# snesbotv2.net
KiCad netlist of a schematic drawn in EAGLE
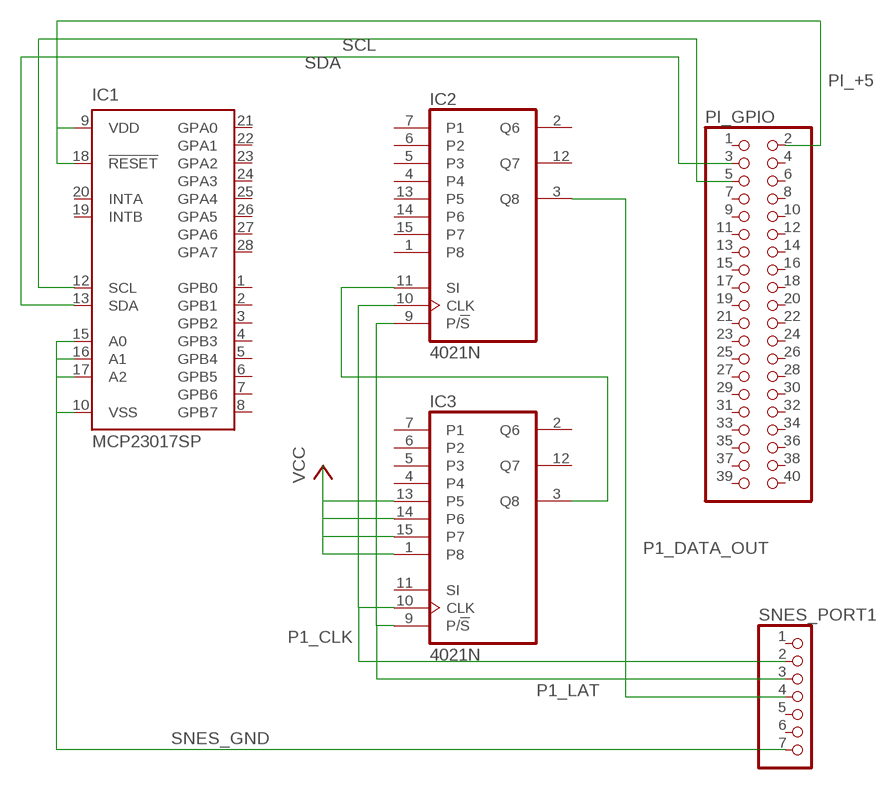
[diagram p0: schematic, sheet 1]

(export (version "E")
  (design (tool "Eeschema 10.0.6"))
  (components
    (comp (ref "IC1")
      (value "MCP23017SP")
      (footprint "eagle-import:DIL28-3")
      (libsource (lib "eagle-import") (part "MCP23017SP"))
    )
    (comp (ref "IC2")
      (value "4021N")
      (footprint "eagle-import:DIL16")
      (libsource (lib "eagle-import") (part "4021N"))
    )
    (comp (ref "IC3")
      (value "4021N")
      (footprint "eagle-import:DIL16")
      (libsource (lib "eagle-import") (part "4021N"))
    )
    (comp (ref "PI_GPIO")
      (value "PINHD-2X20")
      (footprint "eagle-import:2X20")
      (libsource (lib "eagle-import") (part "PINHD-2X20"))
    )
    (comp (ref "SNES_PORT1")
      (value "PINHD-1X7")
      (footprint "eagle-import:1X07")
      (libsource (lib "eagle-import") (part "PINHD-1X7"))
    )
  )
  (nets
    (net (code "1") (name "/P1_CLK") (class "Default")
      (node (ref "IC2") (pin "10") (pinfunction "CLK_10") (pintype "input"))
      (node (ref "IC3") (pin "10") (pinfunction "CLK_10") (pintype "input"))
      (node (ref "SNES_PORT1") (pin "2") (pinfunction "2_2") (pintype "passive"))
    )
    (net (code "2") (name "/P1_DATA_OUT") (class "Default")
      (node (ref "IC2") (pin "3") (pinfunction "Q8_3") (pintype "output"))
      (node (ref "SNES_PORT1") (pin "4") (pinfunction "4_4") (pintype "passive"))
    )
    (net (code "3") (name "/P1_LAT") (class "Default")
      (node (ref "IC2") (pin "9") (pinfunction "P/~{S}_9") (pintype "input"))
      (node (ref "IC3") (pin "9") (pinfunction "P/~{S}_9") (pintype "input"))
      (node (ref "SNES_PORT1") (pin "3") (pinfunction "3_3") (pintype "passive"))
    )
    (net (code "4") (name "/PI_+5") (class "Default")
      (node (ref "IC1") (pin "18") (pinfunction "~{RESET}_18") (pintype "input"))
      (node (ref "IC1") (pin "9") (pinfunction "VDD_9") (pintype "power_in"))
      (node (ref "PI_GPIO") (pin "2") (pinfunction "2_2") (pintype "passive"))
    )
    (net (code "5") (name "/SCL") (class "Default")
      (node (ref "IC1") (pin "12") (pinfunction "SCL_12") (pintype "input"))
      (node (ref "PI_GPIO") (pin "5") (pinfunction "5_5") (pintype "passive"))
    )
    (net (code "6") (name "/SDA") (class "Default")
      (node (ref "IC1") (pin "13") (pinfunction "SDA_13") (pintype "bidirectional"))
      (node (ref "PI_GPIO") (pin "3") (pinfunction "3_3") (pintype "passive"))
    )
    (net (code "7") (name "/SNES_GND") (class "Default")
      (node (ref "IC1") (pin "10") (pinfunction "VSS_10") (pintype "power_in"))
      (node (ref "IC1") (pin "15") (pinfunction "A0_15") (pintype "input"))
      (node (ref "IC1") (pin "16") (pinfunction "A1_16") (pintype "input"))
      (node (ref "IC1") (pin "17") (pinfunction "A2_17") (pintype "input"))
      (node (ref "SNES_PORT1") (pin "7") (pinfunction "7_7") (pintype "passive"))
    )
    (net (code "8") (name "Net-(IC2A-SI)") (class "Default")
      (node (ref "IC2") (pin "11") (pinfunction "SI_11") (pintype "input"))
      (node (ref "IC3") (pin "3") (pinfunction "Q8_3") (pintype "output"))
    )
    (net (code "9") (name "Net-(IC3A-P5)") (class "Default")
      (node (ref "IC3") (pin "1") (pinfunction "P8_1") (pintype "input"))
      (node (ref "IC3") (pin "13") (pinfunction "P5_13") (pintype "input"))
      (node (ref "IC3") (pin "14") (pinfunction "P6_14") (pintype "input"))
      (node (ref "IC3") (pin "15") (pinfunction "P7_15") (pintype "input"))
    )
    (net (code "11") (name "unconnected-(IC1-GPA0-Pad21)") (class "Default")
      (node (ref "IC1") (pin "21") (pinfunction "GPA0_21") (pintype "bidirectional"))
    )
    (net (code "12") (name "unconnected-(IC1-GPA1-Pad22)") (class "Default")
      (node (ref "IC1") (pin "22") (pinfunction "GPA1_22") (pintype "bidirectional"))
    )
    (net (code "13") (name "unconnected-(IC1-GPA2-Pad23)") (class "Default")
      (node (ref "IC1") (pin "23") (pinfunction "GPA2_23") (pintype "bidirectional"))
    )
    (net (code "14") (name "unconnected-(IC1-GPA3-Pad24)") (class "Default")
      (node (ref "IC1") (pin "24") (pinfunction "GPA3_24") (pintype "bidirectional"))
    )
    (net (code "15") (name "unconnected-(IC1-GPA4-Pad25)") (class "Default")
      (node (ref "IC1") (pin "25") (pinfunction "GPA4_25") (pintype "bidirectional"))
    )
    (net (code "16") (name "unconnected-(IC1-GPA5-Pad26)") (class "Default")
      (node (ref "IC1") (pin "26") (pinfunction "GPA5_26") (pintype "bidirectional"))
    )
    (net (code "17") (name "unconnected-(IC1-GPA6-Pad27)") (class "Default")
      (node (ref "IC1") (pin "27") (pinfunction "GPA6_27") (pintype "bidirectional"))
    )
    (net (code "18") (name "unconnected-(IC1-GPA7-Pad28)") (class "Default")
      (node (ref "IC1") (pin "28") (pinfunction "GPA7_28") (pintype "bidirectional"))
    )
    (net (code "19") (name "unconnected-(IC1-GPB0-Pad1)") (class "Default")
      (node (ref "IC1") (pin "1") (pinfunction "GPB0_1") (pintype "bidirectional"))
    )
    (net (code "20") (name "unconnected-(IC1-GPB1-Pad2)") (class "Default")
      (node (ref "IC1") (pin "2") (pinfunction "GPB1_2") (pintype "bidirectional"))
    )
    (net (code "21") (name "unconnected-(IC1-GPB2-Pad3)") (class "Default")
      (node (ref "IC1") (pin "3") (pinfunction "GPB2_3") (pintype "bidirectional"))
    )
    (net (code "22") (name "unconnected-(IC1-GPB3-Pad4)") (class "Default")
      (node (ref "IC1") (pin "4") (pinfunction "GPB3_4") (pintype "bidirectional"))
    )
    (net (code "23") (name "unconnected-(IC1-GPB4-Pad5)") (class "Default")
      (node (ref "IC1") (pin "5") (pinfunction "GPB4_5") (pintype "bidirectional"))
    )
    (net (code "24") (name "unconnected-(IC1-GPB5-Pad6)") (class "Default")
      (node (ref "IC1") (pin "6") (pinfunction "GPB5_6") (pintype "bidirectional"))
    )
    (net (code "25") (name "unconnected-(IC1-GPB6-Pad7)") (class "Default")
      (node (ref "IC1") (pin "7") (pinfunction "GPB6_7") (pintype "bidirectional"))
    )
    (net (code "26") (name "unconnected-(IC1-GPB7-Pad8)") (class "Default")
      (node (ref "IC1") (pin "8") (pinfunction "GPB7_8") (pintype "bidirectional"))
    )
    (net (code "27") (name "unconnected-(IC1-INTA-Pad20)") (class "Default")
      (node (ref "IC1") (pin "20") (pinfunction "INTA_20") (pintype "output"))
    )
    (net (code "28") (name "unconnected-(IC1-INTB-Pad19)") (class "Default")
      (node (ref "IC1") (pin "19") (pinfunction "INTB_19") (pintype "output"))
    )
    (net (code "29") (name "unconnected-(IC2A-P1-Pad7)") (class "Default")
      (node (ref "IC2") (pin "7") (pinfunction "P1_7") (pintype "input"))
    )
    (net (code "30") (name "unconnected-(IC2A-P2-Pad6)") (class "Default")
      (node (ref "IC2") (pin "6") (pinfunction "P2_6") (pintype "input"))
    )
    (net (code "31") (name "unconnected-(IC2A-P3-Pad5)") (class "Default")
      (node (ref "IC2") (pin "5") (pinfunction "P3_5") (pintype "input"))
    )
    (net (code "32") (name "unconnected-(IC2A-P4-Pad4)") (class "Default")
      (node (ref "IC2") (pin "4") (pinfunction "P4_4") (pintype "input"))
    )
    (net (code "33") (name "unconnected-(IC2A-P5-Pad13)") (class "Default")
      (node (ref "IC2") (pin "13") (pinfunction "P5_13") (pintype "input"))
    )
    (net (code "34") (name "unconnected-(IC2A-P6-Pad14)") (class "Default")
      (node (ref "IC2") (pin "14") (pinfunction "P6_14") (pintype "input"))
    )
    (net (code "35") (name "unconnected-(IC2A-P7-Pad15)") (class "Default")
      (node (ref "IC2") (pin "15") (pinfunction "P7_15") (pintype "input"))
    )
    (net (code "36") (name "unconnected-(IC2A-P8-Pad1)") (class "Default")
      (node (ref "IC2") (pin "1") (pinfunction "P8_1") (pintype "input"))
    )
    (net (code "37") (name "unconnected-(IC2A-Q6-Pad2)") (class "Default")
      (node (ref "IC2") (pin "2") (pinfunction "Q6_2") (pintype "output"))
    )
    (net (code "38") (name "unconnected-(IC2A-Q7-Pad12)") (class "Default")
      (node (ref "IC2") (pin "12") (pinfunction "Q7_12") (pintype "output"))
    )
    (net (code "39") (name "unconnected-(IC3A-P1-Pad7)") (class "Default")
      (node (ref "IC3") (pin "7") (pinfunction "P1_7") (pintype "input"))
    )
    (net (code "40") (name "unconnected-(IC3A-P2-Pad6)") (class "Default")
      (node (ref "IC3") (pin "6") (pinfunction "P2_6") (pintype "input"))
    )
    (net (code "41") (name "unconnected-(IC3A-P3-Pad5)") (class "Default")
      (node (ref "IC3") (pin "5") (pinfunction "P3_5") (pintype "input"))
    )
    (net (code "42") (name "unconnected-(IC3A-P4-Pad4)") (class "Default")
      (node (ref "IC3") (pin "4") (pinfunction "P4_4") (pintype "input"))
    )
    (net (code "43") (name "unconnected-(IC3A-Q6-Pad2)") (class "Default")
      (node (ref "IC3") (pin "2") (pinfunction "Q6_2") (pintype "output"))
    )
    (net (code "44") (name "unconnected-(IC3A-Q7-Pad12)") (class "Default")
      (node (ref "IC3") (pin "12") (pinfunction "Q7_12") (pintype "output"))
    )
    (net (code "45") (name "unconnected-(IC3A-SI-Pad11)") (class "Default")
      (node (ref "IC3") (pin "11") (pinfunction "SI_11") (pintype "input"))
    )
    (net (code "46") (name "unconnected-(PI_GPIO-Pad1)") (class "Default")
      (node (ref "PI_GPIO") (pin "1") (pinfunction "1_1") (pintype "passive"))
    )
    (net (code "47") (name "unconnected-(PI_GPIO-Pad4)") (class "Default")
      (node (ref "PI_GPIO") (pin "4") (pinfunction "4_4") (pintype "passive"))
    )
    (net (code "48") (name "unconnected-(PI_GPIO-Pad6)") (class "Default")
      (node (ref "PI_GPIO") (pin "6") (pinfunction "6_6") (pintype "passive"))
    )
    (net (code "49") (name "unconnected-(PI_GPIO-Pad7)") (class "Default")
      (node (ref "PI_GPIO") (pin "7") (pinfunction "7_7") (pintype "passive"))
    )
    (net (code "50") (name "unconnected-(PI_GPIO-Pad8)") (class "Default")
      (node (ref "PI_GPIO") (pin "8") (pinfunction "8_8") (pintype "passive"))
    )
    (net (code "51") (name "unconnected-(PI_GPIO-Pad9)") (class "Default")
      (node (ref "PI_GPIO") (pin "9") (pinfunction "9_9") (pintype "passive"))
    )
    (net (code "52") (name "unconnected-(PI_GPIO-Pad10)") (class "Default")
      (node (ref "PI_GPIO") (pin "10") (pinfunction "10_10") (pintype "passive"))
    )
    (net (code "53") (name "unconnected-(PI_GPIO-Pad11)") (class "Default")
      (node (ref "PI_GPIO") (pin "11") (pinfunction "11_11") (pintype "passive"))
    )
    (net (code "54") (name "unconnected-(PI_GPIO-Pad12)") (class "Default")
      (node (ref "PI_GPIO") (pin "12") (pinfunction "12_12") (pintype "passive"))
    )
    (net (code "55") (name "unconnected-(PI_GPIO-Pad13)") (class "Default")
      (node (ref "PI_GPIO") (pin "13") (pinfunction "13_13") (pintype "passive"))
    )
    (net (code "56") (name "unconnected-(PI_GPIO-Pad14)") (class "Default")
      (node (ref "PI_GPIO") (pin "14") (pinfunction "14_14") (pintype "passive"))
    )
    (net (code "57") (name "unconnected-(PI_GPIO-Pad15)") (class "Default")
      (node (ref "PI_GPIO") (pin "15") (pinfunction "15_15") (pintype "passive"))
    )
    (net (code "58") (name "unconnected-(PI_GPIO-Pad16)") (class "Default")
      (node (ref "PI_GPIO") (pin "16") (pinfunction "16_16") (pintype "passive"))
    )
    (net (code "59") (name "unconnected-(PI_GPIO-Pad17)") (class "Default")
      (node (ref "PI_GPIO") (pin "17") (pinfunction "17_17") (pintype "passive"))
    )
    (net (code "60") (name "unconnected-(PI_GPIO-Pad18)") (class "Default")
      (node (ref "PI_GPIO") (pin "18") (pinfunction "18_18") (pintype "passive"))
    )
    (net (code "61") (name "unconnected-(PI_GPIO-Pad19)") (class "Default")
      (node (ref "PI_GPIO") (pin "19") (pinfunction "19_19") (pintype "passive"))
    )
    (net (code "62") (name "unconnected-(PI_GPIO-Pad20)") (class "Default")
      (node (ref "PI_GPIO") (pin "20") (pinfunction "20_20") (pintype "passive"))
    )
    (net (code "63") (name "unconnected-(PI_GPIO-Pad21)") (class "Default")
      (node (ref "PI_GPIO") (pin "21") (pinfunction "21_21") (pintype "passive"))
    )
    (net (code "64") (name "unconnected-(PI_GPIO-Pad22)") (class "Default")
      (node (ref "PI_GPIO") (pin "22") (pinfunction "22_22") (pintype "passive"))
    )
    (net (code "65") (name "unconnected-(PI_GPIO-Pad23)") (class "Default")
      (node (ref "PI_GPIO") (pin "23") (pinfunction "23_23") (pintype "passive"))
    )
    (net (code "66") (name "unconnected-(PI_GPIO-Pad24)") (class "Default")
      (node (ref "PI_GPIO") (pin "24") (pinfunction "24_24") (pintype "passive"))
    )
    (net (code "67") (name "unconnected-(PI_GPIO-Pad25)") (class "Default")
      (node (ref "PI_GPIO") (pin "25") (pinfunction "25_25") (pintype "passive"))
    )
    (net (code "68") (name "unconnected-(PI_GPIO-Pad26)") (class "Default")
      (node (ref "PI_GPIO") (pin "26") (pinfunction "26_26") (pintype "passive"))
    )
    (net (code "69") (name "unconnected-(PI_GPIO-Pad27)") (class "Default")
      (node (ref "PI_GPIO") (pin "27") (pinfunction "27_27") (pintype "passive"))
    )
    (net (code "70") (name "unconnected-(PI_GPIO-Pad28)") (class "Default")
      (node (ref "PI_GPIO") (pin "28") (pinfunction "28_28") (pintype "passive"))
    )
    (net (code "71") (name "unconnected-(PI_GPIO-Pad29)") (class "Default")
      (node (ref "PI_GPIO") (pin "29") (pinfunction "29_29") (pintype "passive"))
    )
    (net (code "72") (name "unconnected-(PI_GPIO-Pad30)") (class "Default")
      (node (ref "PI_GPIO") (pin "30") (pinfunction "30_30") (pintype "passive"))
    )
    (net (code "73") (name "unconnected-(PI_GPIO-Pad31)") (class "Default")
      (node (ref "PI_GPIO") (pin "31") (pinfunction "31_31") (pintype "passive"))
    )
    (net (code "74") (name "unconnected-(PI_GPIO-Pad32)") (class "Default")
      (node (ref "PI_GPIO") (pin "32") (pinfunction "32_32") (pintype "passive"))
    )
    (net (code "75") (name "unconnected-(PI_GPIO-Pad33)") (class "Default")
      (node (ref "PI_GPIO") (pin "33") (pinfunction "33_33") (pintype "passive"))
    )
    (net (code "76") (name "unconnected-(PI_GPIO-Pad34)") (class "Default")
      (node (ref "PI_GPIO") (pin "34") (pinfunction "34_34") (pintype "passive"))
    )
    (net (code "77") (name "unconnected-(PI_GPIO-Pad35)") (class "Default")
      (node (ref "PI_GPIO") (pin "35") (pinfunction "35_35") (pintype "passive"))
    )
    (net (code "78") (name "unconnected-(PI_GPIO-Pad36)") (class "Default")
      (node (ref "PI_GPIO") (pin "36") (pinfunction "36_36") (pintype "passive"))
    )
    (net (code "79") (name "unconnected-(PI_GPIO-Pad37)") (class "Default")
      (node (ref "PI_GPIO") (pin "37") (pinfunction "37_37") (pintype "passive"))
    )
    (net (code "80") (name "unconnected-(PI_GPIO-Pad38)") (class "Default")
      (node (ref "PI_GPIO") (pin "38") (pinfunction "38_38") (pintype "passive"))
    )
    (net (code "81") (name "unconnected-(PI_GPIO-Pad39)") (class "Default")
      (node (ref "PI_GPIO") (pin "39") (pinfunction "39_39") (pintype "passive"))
    )
    (net (code "82") (name "unconnected-(PI_GPIO-Pad40)") (class "Default")
      (node (ref "PI_GPIO") (pin "40") (pinfunction "40_40") (pintype "passive"))
    )
    (net (code "83") (name "unconnected-(SNES_PORT1-Pad1)") (class "Default")
      (node (ref "SNES_PORT1") (pin "1") (pinfunction "1_1") (pintype "passive"))
    )
    (net (code "84") (name "unconnected-(SNES_PORT1-Pad5)") (class "Default")
      (node (ref "SNES_PORT1") (pin "5") (pinfunction "5_5") (pintype "passive"))
    )
    (net (code "85") (name "unconnected-(SNES_PORT1-Pad6)") (class "Default")
      (node (ref "SNES_PORT1") (pin "6") (pinfunction "6_6") (pintype "passive"))
    )
  )
)
